# 1s.net
KiCad netlist of a schematic drawn in Altium Designer
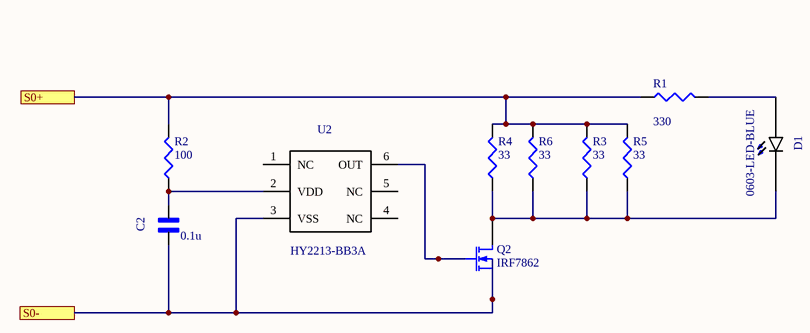
[diagram p0: 1s.SchDoc]

(export (version "E")
  (design (tool "Eeschema 10.0.6"))
  (components
    (comp (ref "C2")
      (value "0.1u")
      (footprint "*CAPC1608X90")
      (description "Cap Thin Film 0.1uf 50v 0603")
      (fields (field (name "MF") "AVX") (field (name "MP") "GX035C104MAT2-500 or CL10B104JB8NNNC"))
      (libsource (lib "lib") (part "GX035C104MAT2-500"))
    )
    (comp (ref "D1")
      (value "0603-LED-BLUE")
      (footprint "*LEDM1608X80_LTE-C1906R-14(Primary)")
      (description "LED IrLED Chip LED 2-Pin SMD T/R")
      (libsource (lib "lib") (part "LTE-C1906R-14"))
    )
    (comp (ref "Q2")
      (value "IRF7862")
      (footprint "*SO-08")
      (description "N-Channel MOSFET")
      (fields (field (name "PUBLISHER") "Altium Limited"))
      (libsource (lib "lib") (part "IRF7862"))
    )
    (comp (ref "R1")
      (value "330")
      (footprint "J1-0603")
      (description "330 Ohms ±1% 0.1W, 1/10W Chip Resistor 0603 (1608 Metric) Thick Film")
      (fields (field (name "MF") "Yageo or NXP") (field (name "MP") "RC0603FR-07330RL"))
      (libsource (lib "lib") (part "RC0603FR-07330RL"))
    )
    (comp (ref "R2")
      (value "100")
      (footprint "J1-0603")
      (description "Resistor")
      (fields (field (name "Comment") "Res3") (field (name "PUBLISHER") "Altium Limited"))
      (libsource (lib "Miscellaneous Devices") (part "Res3"))
    )
    (comp (ref "R3")
      (value "33")
      (footprint "12Z-2010")
      (description "Resistor")
      (fields (field (name "Comment") "Res3") (field (name "PUBLISHER") "Altium Limited"))
      (libsource (lib "Miscellaneous Devices") (part "Res3"))
    )
    (comp (ref "R4")
      (value "33")
      (footprint "12Z-2010")
      (description "Resistor")
      (fields (field (name "Comment") "Res3") (field (name "PUBLISHER") "Altium Limited"))
      (libsource (lib "Miscellaneous Devices") (part "Res3"))
    )
    (comp (ref "R5")
      (value "33")
      (footprint "12Z-2010")
      (description "Resistor")
      (fields (field (name "Comment") "Res3") (field (name "PUBLISHER") "Altium Limited"))
      (libsource (lib "Miscellaneous Devices") (part "Res3"))
    )
    (comp (ref "R6")
      (value "33")
      (footprint "12Z-2010")
      (description "Resistor")
      (fields (field (name "Comment") "Res3") (field (name "PUBLISHER") "Altium Limited"))
      (libsource (lib "Miscellaneous Devices") (part "Res3"))
    )
    (comp (ref "U2")
      (value "HY2213-BB3A")
      (footprint "sot23-6")
      (fields (field (name "MF") "infineon") (field (name "MP") "IRS10752LTRPBF"))
      (libsource (lib "lib") (part "HY2213-BB3A"))
    )
  )
  (nets
    (net (code "1") (name "/S0+") (class "Default")
      (node (ref "R1") (pin "1") (pinfunction "1_1") (pintype "passive"))
      (node (ref "R2") (pin "2") (pinfunction "2_2") (pintype "passive"))
      (node (ref "R3") (pin "2") (pinfunction "2_2") (pintype "passive"))
      (node (ref "R4") (pin "2") (pinfunction "2_2") (pintype "passive"))
      (node (ref "R5") (pin "2") (pinfunction "2_2") (pintype "passive"))
      (node (ref "R6") (pin "2") (pinfunction "2_2") (pintype "passive"))
    )
    (net (code "2") (name "/S0-") (class "Default")
      (node (ref "C2") (pin "2") (pinfunction "2_2") (pintype "passive"))
      (node (ref "Q2") (pin "S") (pinfunction "S_S") (pintype "passive"))
      (node (ref "U2") (pin "3") (pinfunction "VSS_3") (pintype "power_in"))
    )
    (net (code "3") (name "Net-(D1-PadA)") (class "Default")
      (node (ref "D1") (pin "A") (pinfunction "A_A") (pintype "passive"))
      (node (ref "R1") (pin "2") (pinfunction "2_2") (pintype "passive"))
    )
    (net (code "4") (name "Net-(D1-PadC)") (class "Default")
      (node (ref "D1") (pin "C") (pinfunction "C_C") (pintype "passive"))
      (node (ref "Q2") (pin "D") (pinfunction "D_D") (pintype "passive"))
      (node (ref "R3") (pin "1") (pinfunction "1_1") (pintype "passive"))
      (node (ref "R4") (pin "1") (pinfunction "1_1") (pintype "passive"))
      (node (ref "R5") (pin "1") (pinfunction "1_1") (pintype "passive"))
      (node (ref "R6") (pin "1") (pinfunction "1_1") (pintype "passive"))
    )
    (net (code "5") (name "Net-(U2-OUT)") (class "Default")
      (node (ref "Q2") (pin "G") (pinfunction "G_G") (pintype "passive"))
      (node (ref "U2") (pin "6") (pinfunction "OUT_6") (pintype "power_in"))
    )
    (net (code "6") (name "Net-(U2-VDD)") (class "Default")
      (node (ref "C2") (pin "1") (pinfunction "1_1") (pintype "passive"))
      (node (ref "R2") (pin "1") (pinfunction "1_1") (pintype "passive"))
      (node (ref "U2") (pin "2") (pinfunction "VDD_2") (pintype "passive"))
    )
    (net (code "7") (name "unconnected-(U2-NC-Pad1)") (class "Default")
      (node (ref "U2") (pin "1") (pinfunction "NC_1") (pintype "power_in"))
    )
    (net (code "8") (name "unconnected-(U2-NC-Pad4)") (class "Default")
      (node (ref "U2") (pin "4") (pinfunction "NC_4") (pintype "power_in"))
    )
    (net (code "9") (name "unconnected-(U2-NC-Pad5)") (class "Default")
      (node (ref "U2") (pin "5") (pinfunction "NC_5") (pintype "passive"))
    )
  )
)
